# ranback_top.net
KiCad netlist of a schematic drawn in EAGLE
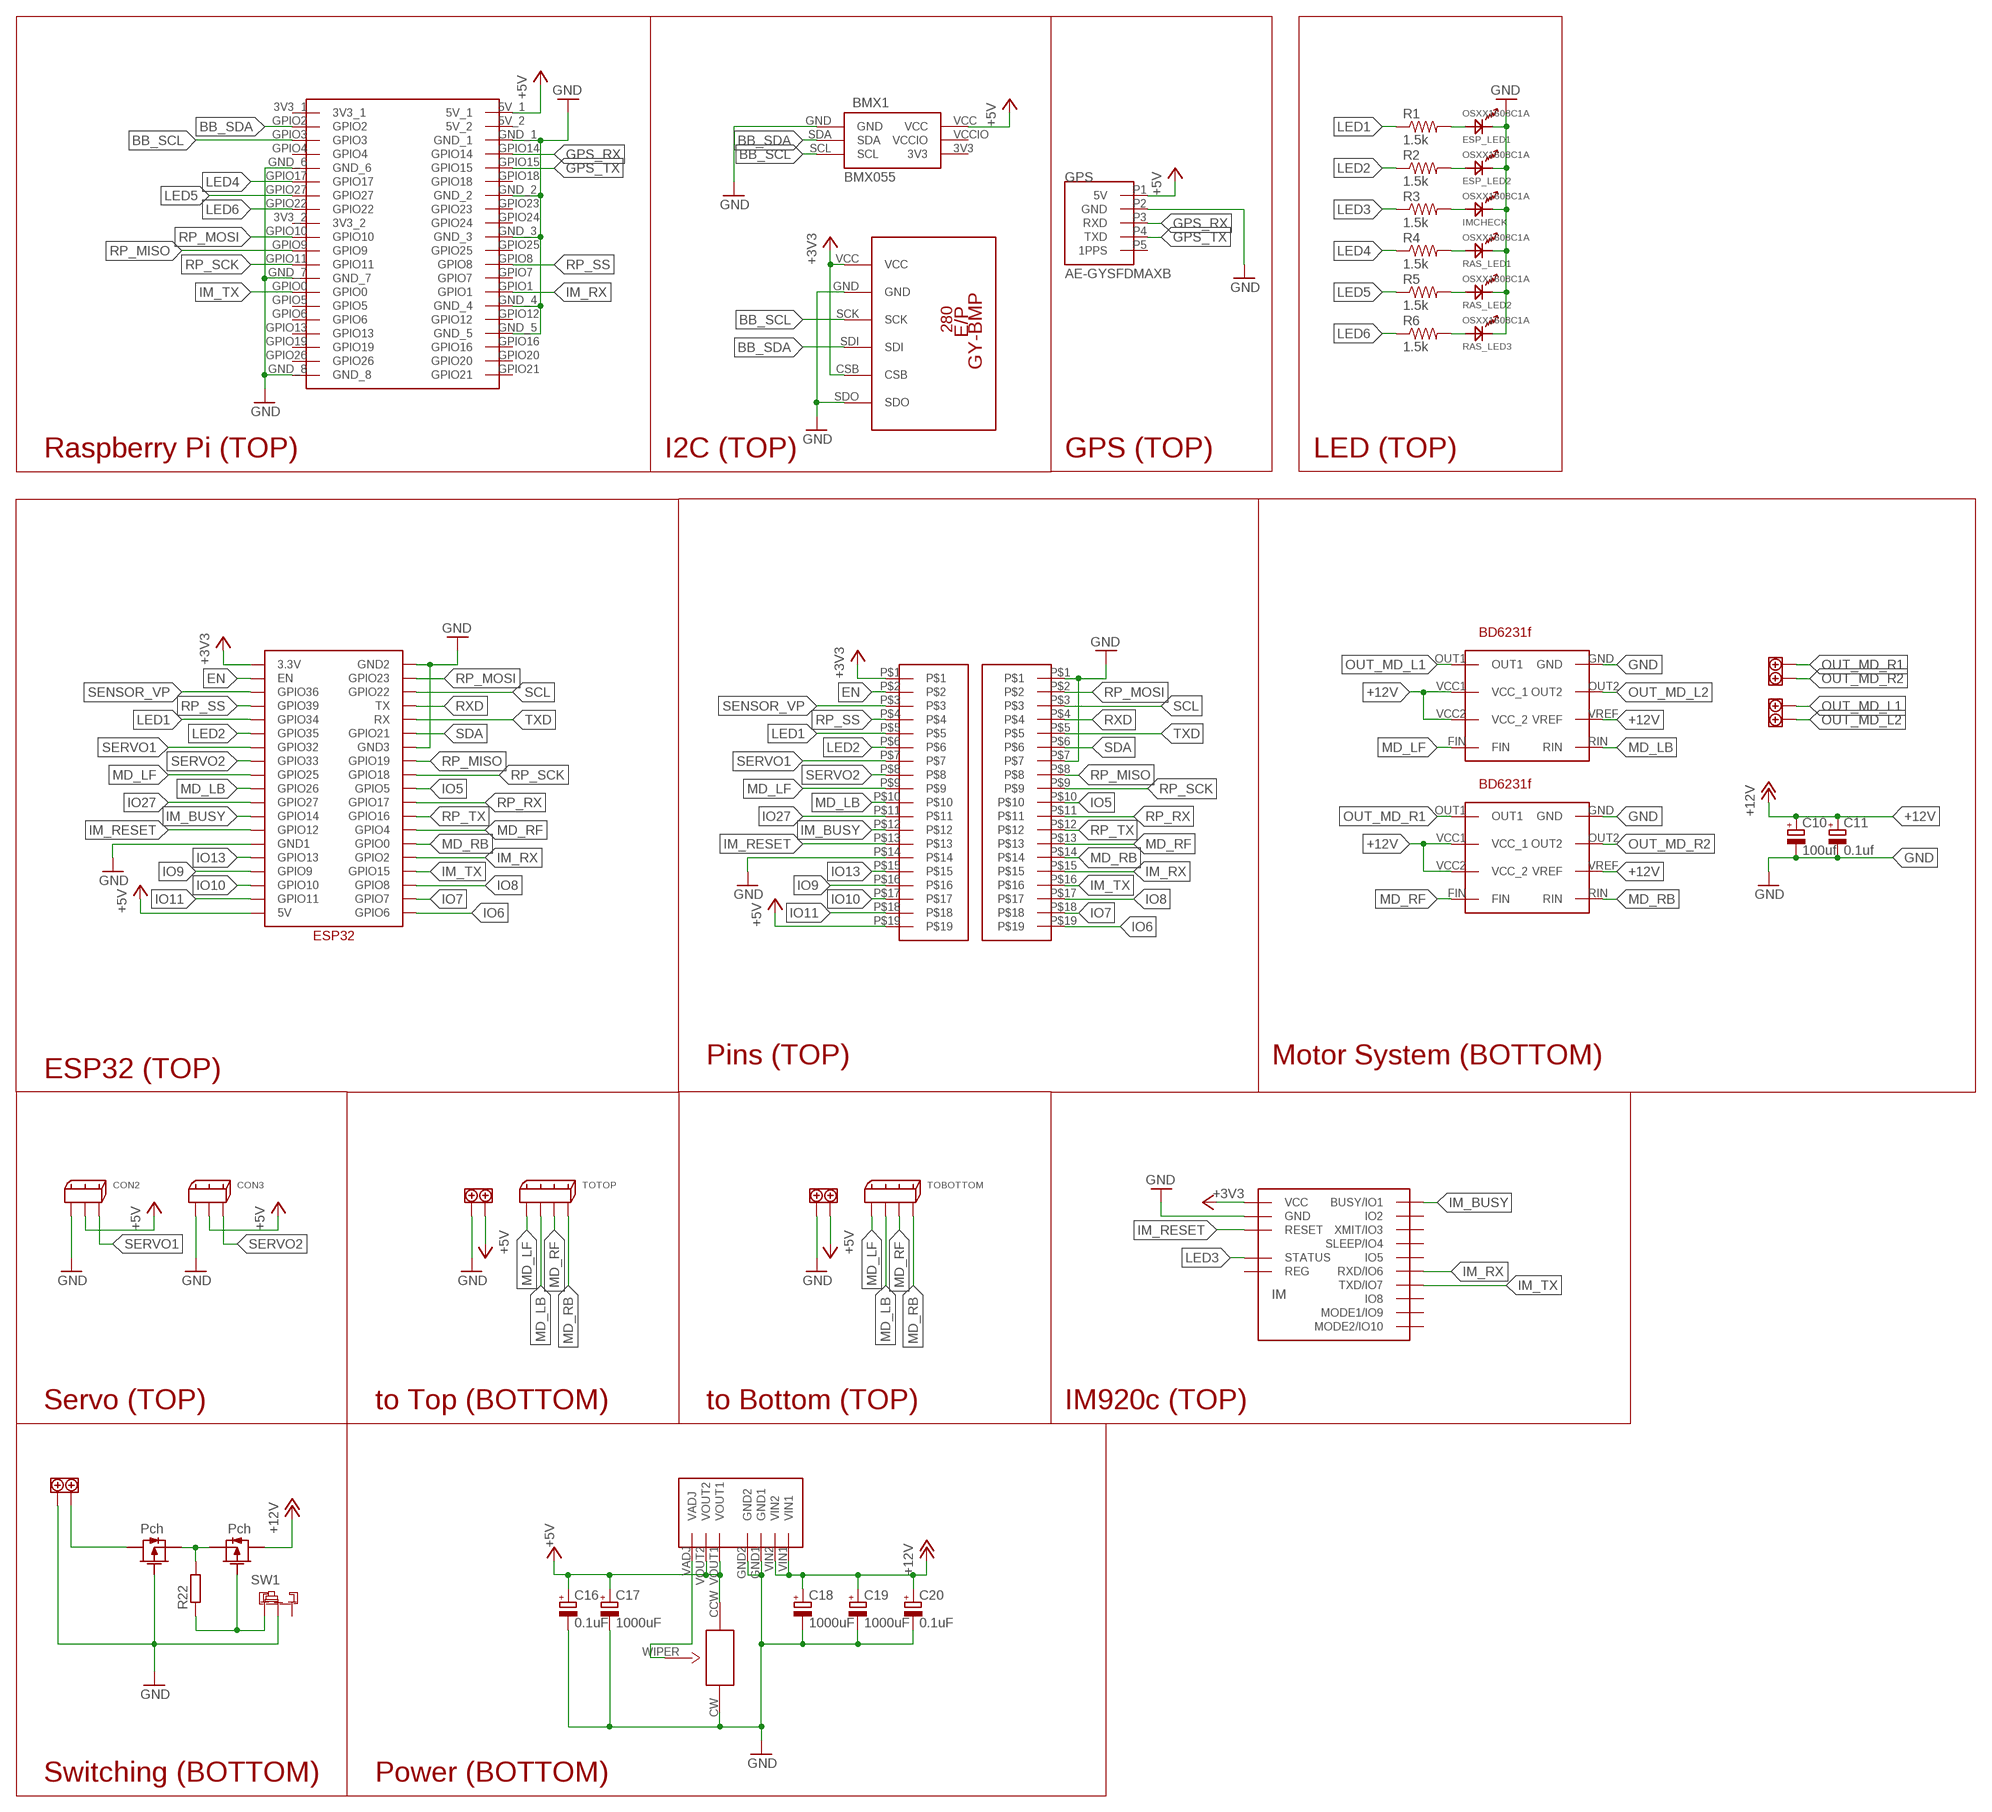
[diagram p0: schematic, sheet 1]

(export (version "E")
  (design (tool "Eeschema 10.0.6"))
  (components
    (comp (ref "100KR1")
      (value "100kR")
      (footprint "eagle-import:3362P")
      (libsource (lib "eagle-import") (part "3362P"))
    )
    (comp (ref "BMX1")
      (value "BMX055")
      (footprint "eagle-import:BMX055")
      (libsource (lib "eagle-import") (part "BMX055"))
    )
    (comp (ref "C10")
      (value "100uf")
      (footprint "eagle-import:E2,5-7")
      (libsource (lib "eagle-import") (part "CPOL-EUE2.5-7"))
    )
    (comp (ref "C11")
      (value "0.1uf")
      (footprint "eagle-import:E2,5-7")
      (libsource (lib "eagle-import") (part "CPOL-EUE2.5-7"))
    )
    (comp (ref "C16")
      (value "0.1uF")
      (footprint "eagle-import:E2,5-7")
      (libsource (lib "eagle-import") (part "CPOL-EUE2.5-7"))
    )
    (comp (ref "C17")
      (value "1000uF")
      (footprint "eagle-import:E5-10,5")
      (libsource (lib "eagle-import") (part "CPOL-EUE5-10.5"))
    )
    (comp (ref "C18")
      (value "1000uF")
      (footprint "eagle-import:E5-10,5")
      (libsource (lib "eagle-import") (part "CPOL-EUE5-10.5"))
    )
    (comp (ref "C19")
      (value "1000uF")
      (footprint "eagle-import:E5-10,5")
      (libsource (lib "eagle-import") (part "CPOL-EUE5-10.5"))
    )
    (comp (ref "C20")
      (value "0.1uF")
      (footprint "eagle-import:E2,5-7")
      (libsource (lib "eagle-import") (part "CPOL-EUE2.5-7"))
    )
    (comp (ref "CON2")
      (value "2.5_MINI-SPOX_3PIN")
      (footprint "eagle-import:2.5_MINI-SPOX_3PIN")
      (libsource (lib "eagle-import") (part "2.5_MINI-SPOX_3PIN"))
    )
    (comp (ref "CON3")
      (value "2.5_MINI-SPOX_3PIN")
      (footprint "eagle-import:2.5_MINI-SPOX_3PIN")
      (libsource (lib "eagle-import") (part "2.5_MINI-SPOX_3PIN"))
    )
    (comp (ref "ESP_LED1")
      (value "OSXX1608C1A")
      (footprint "eagle-import:OSXX1608C1A")
      (libsource (lib "eagle-import") (part "OSXX1608C1A"))
    )
    (comp (ref "ESP_LED2")
      (value "OSXX1608C1A")
      (footprint "eagle-import:OSXX1608C1A")
      (libsource (lib "eagle-import") (part "OSXX1608C1A"))
    )
    (comp (ref "GPS")
      (value "AE-GYSFDMAXB")
      (footprint "eagle-import:AE-GYSFDMAXB")
      (libsource (lib "eagle-import") (part "AE-GYSFDMAXB"))
    )
    (comp (ref "IM")
      (value "IM920C")
      (footprint "eagle-import:IM920C")
      (libsource (lib "eagle-import") (part "IM920C"))
    )
    (comp (ref "IMCHECK")
      (value "OSXX1608C1A")
      (footprint "eagle-import:OSXX1608C1A")
      (libsource (lib "eagle-import") (part "OSXX1608C1A"))
    )
    (comp (ref "MD_L")
      (value "BD6231F")
      (footprint "eagle-import:BD6231F")
      (libsource (lib "eagle-import") (part "BD6231F"))
    )
    (comp (ref "MD_R")
      (value "BD6231F")
      (footprint "eagle-import:BD6231F")
      (libsource (lib "eagle-import") (part "BD6231F"))
    )
    (comp (ref "PIN_L")
      (value "19_2.54")
      (footprint "eagle-import:19_2.54")
      (libsource (lib "eagle-import") (part "19_2.54"))
    )
    (comp (ref "PIN_R")
      (value "19_2.54")
      (footprint "eagle-import:19_2.54")
      (libsource (lib "eagle-import") (part "19_2.54"))
    )
    (comp (ref "R1")
      (value "1.5k")
      (footprint "eagle-import:R0603")
      (libsource (lib "eagle-import") (part "R-US_R0603"))
    )
    (comp (ref "R2")
      (value "1.5k")
      (footprint "eagle-import:R0603")
      (libsource (lib "eagle-import") (part "R-US_R0603"))
    )
    (comp (ref "R3")
      (value "1.5k")
      (footprint "eagle-import:R0603")
      (libsource (lib "eagle-import") (part "R-US_R0603"))
    )
    (comp (ref "R4")
      (value "1.5k")
      (footprint "eagle-import:R0603")
      (libsource (lib "eagle-import") (part "R-US_R0603"))
    )
    (comp (ref "R5")
      (value "1.5k")
      (footprint "eagle-import:R0603")
      (libsource (lib "eagle-import") (part "R-US_R0603"))
    )
    (comp (ref "R6")
      (value "1.5k")
      (footprint "eagle-import:R0603")
      (libsource (lib "eagle-import") (part "R-US_R0603"))
    )
    (comp (ref "R22")
      (value "R-EU_0207/10")
      (footprint "eagle-import:0207_10")
      (libsource (lib "eagle-import") (part "R-EU_0207/10"))
    )
    (comp (ref "RASPBERRYPI_4B")
      (value "RASPBERRYPI4B")
      (footprint "eagle-import:RASPBERRYPI4B")
      (libsource (lib "eagle-import") (part "RASPBERRYPI4B"))
    )
    (comp (ref "RAS_LED1")
      (value "OSXX1608C1A")
      (footprint "eagle-import:OSXX1608C1A")
      (libsource (lib "eagle-import") (part "OSXX1608C1A"))
    )
    (comp (ref "RAS_LED2")
      (value "OSXX1608C1A")
      (footprint "eagle-import:OSXX1608C1A")
      (libsource (lib "eagle-import") (part "OSXX1608C1A"))
    )
    (comp (ref "RAS_LED3")
      (value "OSXX1608C1A")
      (footprint "eagle-import:OSXX1608C1A")
      (libsource (lib "eagle-import") (part "OSXX1608C1A"))
    )
    (comp (ref "SW1")
      (value "SRIDE_SWITCH")
      (footprint "eagle-import:SRIDE_SWITCH")
      (libsource (lib "eagle-import") (part "SRIDE_SWITCH"))
    )
    (comp (ref "TM1")
      (value "TERMINAL_SLOPED_2PIN")
      (footprint "eagle-import:TERMINAL_SLOPED_2PIN")
      (libsource (lib "eagle-import") (part "TERMINAL_SLOPED_2PIN"))
    )
    (comp (ref "TM2")
      (value "TERMINAL_SLOPED_2PIN")
      (footprint "eagle-import:TERMINAL_SLOPED_2PIN")
      (libsource (lib "eagle-import") (part "TERMINAL_SLOPED_2PIN"))
    )
    (comp (ref "TM3")
      (value "TERMINAL_SLOPED_2PIN")
      (footprint "eagle-import:TERMINAL_SLOPED_2PIN")
      (libsource (lib "eagle-import") (part "TERMINAL_SLOPED_2PIN"))
    )
    (comp (ref "TM4")
      (value "TERMINAL_SLOPED_2PIN")
      (footprint "eagle-import:TERMINAL_SLOPED_2PIN")
      (libsource (lib "eagle-import") (part "TERMINAL_SLOPED_2PIN"))
    )
    (comp (ref "TM5")
      (value "TERMINAL_SLOPED_2PIN")
      (footprint "eagle-import:TERMINAL_SLOPED_2PIN")
      (libsource (lib "eagle-import") (part "TERMINAL_SLOPED_2PIN"))
    )
    (comp (ref "TOBOTTOM")
      (value "2.5_MINI-SPOX_4PIN")
      (footprint "eagle-import:2.5_MINI-SPOX_4PIN")
      (libsource (lib "eagle-import") (part "2.5_MINI-SPOX_4PIN"))
    )
    (comp (ref "TOTOP")
      (value "2.5_MINI-SPOX_4PIN")
      (footprint "eagle-import:2.5_MINI-SPOX_4PIN")
      (libsource (lib "eagle-import") (part "2.5_MINI-SPOX_4PIN"))
    )
    (comp (ref "U$2")
      (value "ESP32")
      (footprint "eagle-import:ESP32")
      (libsource (lib "eagle-import") (part "ESP32"))
    )
    (comp (ref "U$7")
      (value "2SJ681-PCH")
      (footprint "eagle-import:2SJ681")
      (libsource (lib "eagle-import") (part "2SJ681-PCH"))
    )
    (comp (ref "U$8")
      (value "5V3A_KIC-053")
      (footprint "eagle-import:5V3A_KIC-053")
      (libsource (lib "eagle-import") (part "5V3A_KIC-053"))
    )
    (comp (ref "U$9")
      (value "GY-BPM280")
      (footprint "eagle-import:GY-BMP280-FOOTPRINT")
      (libsource (lib "eagle-import") (part "GY-BPM280"))
    )
    (comp (ref "U$10")
      (value "2SJ681-PCH")
      (footprint "eagle-import:2SJ681")
      (libsource (lib "eagle-import") (part "2SJ681-PCH"))
    )
  )
  (nets
    (net (code "1") (name "+3V3") (class "Default")
      (node (ref "IM") (pin "$P17") (pinfunction "VCC_$P17") (pintype "bidirectional"))
      (node (ref "PIN_L") (pin "P$1") (pinfunction "P$1_P$1") (pintype "bidirectional"))
      (node (ref "U$2") (pin "3.3V") (pinfunction "3.3V_3.3V") (pintype "bidirectional"))
      (node (ref "U$9") (pin "CSB") (pinfunction "CSB_CSB") (pintype "bidirectional"))
      (node (ref "U$9") (pin "VCC") (pinfunction "VCC_VCC") (pintype "bidirectional"))
    )
    (net (code "2") (name "+5V") (class "Default")
      (node (ref "100KR1") (pin "CCW") (pinfunction "CCW_CCW") (pintype "bidirectional"))
      (node (ref "BMX1") (pin "VCC") (pinfunction "VCC_VCC") (pintype "power_in"))
      (node (ref "C16") (pin "+") (pinfunction "+_+") (pintype "passive"))
      (node (ref "C17") (pin "+") (pinfunction "+_+") (pintype "passive"))
      (node (ref "CON2") (pin "2") (pinfunction "2_2") (pintype "bidirectional"))
      (node (ref "CON3") (pin "2") (pinfunction "2_2") (pintype "bidirectional"))
      (node (ref "GPS") (pin "P1") (pinfunction "5V_P1") (pintype "bidirectional"))
      (node (ref "PIN_L") (pin "P$19") (pinfunction "P$19_P$19") (pintype "bidirectional"))
      (node (ref "RASPBERRYPI_4B") (pin "5V_1") (pinfunction "5V_1_5V_1") (pintype "bidirectional"))
      (node (ref "TM4") (pin "1") (pinfunction "1_1") (pintype "bidirectional"))
      (node (ref "TM5") (pin "1") (pinfunction "1_1") (pintype "bidirectional"))
      (node (ref "U$2") (pin "5V") (pinfunction "5V_5V") (pintype "bidirectional"))
      (node (ref "U$8") (pin "VOUT1") (pinfunction "VOUT1_VOUT1") (pintype "bidirectional"))
      (node (ref "U$8") (pin "VOUT2") (pinfunction "VOUT2_VOUT2") (pintype "bidirectional"))
    )
    (net (code "3") (name "+12V") (class "Default")
      (node (ref "C10") (pin "+") (pinfunction "+_+") (pintype "passive"))
      (node (ref "C11") (pin "+") (pinfunction "+_+") (pintype "passive"))
      (node (ref "C18") (pin "+") (pinfunction "+_+") (pintype "passive"))
      (node (ref "C19") (pin "+") (pinfunction "+_+") (pintype "passive"))
      (node (ref "C20") (pin "+") (pinfunction "+_+") (pintype "passive"))
      (node (ref "MD_L") (pin "VCC1") (pinfunction "VCC_1_VCC1") (pintype "bidirectional"))
      (node (ref "MD_L") (pin "VCC2") (pinfunction "VCC_2_VCC2") (pintype "bidirectional"))
      (node (ref "MD_L") (pin "VREF") (pinfunction "VREF_VREF") (pintype "bidirectional"))
      (node (ref "MD_R") (pin "VCC1") (pinfunction "VCC_1_VCC1") (pintype "bidirectional"))
      (node (ref "MD_R") (pin "VCC2") (pinfunction "VCC_2_VCC2") (pintype "bidirectional"))
      (node (ref "MD_R") (pin "VREF") (pinfunction "VREF_VREF") (pintype "bidirectional"))
      (node (ref "U$10") (pin "DRAIN") (pinfunction "DRAIN_DRAIN") (pintype "bidirectional"))
      (node (ref "U$8") (pin "VIN1") (pinfunction "VIN1_VIN1") (pintype "bidirectional"))
      (node (ref "U$8") (pin "VIN2") (pinfunction "VIN2_VIN2") (pintype "bidirectional"))
    )
    (net (code "4") (name "/3V3") (class "Default")
      (node (ref "BMX1") (pin "3V3") (pinfunction "3V3_3V3") (pintype "power_in"))
    )
    (net (code "5") (name "/VCCIO") (class "Default")
      (node (ref "BMX1") (pin "VCCIO") (pinfunction "VCCIO_VCCIO") (pintype "power_in"))
    )
    (net (code "6") (name "BB_SCL") (class "Default")
      (node (ref "BMX1") (pin "SCL") (pinfunction "SCL_SCL") (pintype "bidirectional"))
      (node (ref "RASPBERRYPI_4B") (pin "GPIO3") (pinfunction "GPIO3_GPIO3") (pintype "bidirectional"))
      (node (ref "U$9") (pin "SCK") (pinfunction "SCK_SCK") (pintype "bidirectional"))
    )
    (net (code "7") (name "BB_SDA") (class "Default")
      (node (ref "BMX1") (pin "SDA") (pinfunction "SDA_SDA") (pintype "bidirectional"))
      (node (ref "RASPBERRYPI_4B") (pin "GPIO2") (pinfunction "GPIO2_GPIO2") (pintype "bidirectional"))
      (node (ref "U$9") (pin "SDI") (pinfunction "SDI_SDI") (pintype "bidirectional"))
    )
    (net (code "8") (name "EN") (class "Default")
      (node (ref "PIN_L") (pin "P$2") (pinfunction "P$2_P$2") (pintype "bidirectional"))
      (node (ref "U$2") (pin "EN") (pinfunction "EN_EN") (pintype "bidirectional"))
    )
    (net (code "9") (name "GND") (class "Default")
      (node (ref "100KR1") (pin "CW") (pinfunction "CW_CW") (pintype "bidirectional"))
      (node (ref "BMX1") (pin "GND") (pinfunction "GND_GND") (pintype "power_in"))
      (node (ref "C10") (pin "-") (pinfunction "-_-") (pintype "passive"))
      (node (ref "C11") (pin "-") (pinfunction "-_-") (pintype "passive"))
      (node (ref "C16") (pin "-") (pinfunction "-_-") (pintype "passive"))
      (node (ref "C17") (pin "-") (pinfunction "-_-") (pintype "passive"))
      (node (ref "C18") (pin "-") (pinfunction "-_-") (pintype "passive"))
      (node (ref "C19") (pin "-") (pinfunction "-_-") (pintype "passive"))
      (node (ref "C20") (pin "-") (pinfunction "-_-") (pintype "passive"))
      (node (ref "CON2") (pin "1") (pinfunction "1_1") (pintype "bidirectional"))
      (node (ref "CON3") (pin "1") (pinfunction "1_1") (pintype "bidirectional"))
      (node (ref "ESP_LED1") (pin "CT") (pinfunction "CT_CT") (pintype "bidirectional"))
      (node (ref "ESP_LED2") (pin "CT") (pinfunction "CT_CT") (pintype "bidirectional"))
      (node (ref "GPS") (pin "P2") (pinfunction "GND_P2") (pintype "bidirectional"))
      (node (ref "IM") (pin "$P18") (pinfunction "GND_$P18") (pintype "bidirectional"))
      (node (ref "IMCHECK") (pin "CT") (pinfunction "CT_CT") (pintype "bidirectional"))
      (node (ref "MD_L") (pin "GND") (pinfunction "GND_GND") (pintype "bidirectional"))
      (node (ref "MD_R") (pin "GND") (pinfunction "GND_GND") (pintype "bidirectional"))
      (node (ref "PIN_L") (pin "P$14") (pinfunction "P$14_P$14") (pintype "bidirectional"))
      (node (ref "PIN_R") (pin "P$1") (pinfunction "P$1_P$1") (pintype "bidirectional"))
      (node (ref "PIN_R") (pin "P$7") (pinfunction "P$7_P$7") (pintype "bidirectional"))
      (node (ref "RASPBERRYPI_4B") (pin "GND_1") (pinfunction "GND_1_GND_1") (pintype "bidirectional"))
      (node (ref "RASPBERRYPI_4B") (pin "GND_2") (pinfunction "GND_2_GND_2") (pintype "bidirectional"))
      (node (ref "RASPBERRYPI_4B") (pin "GND_3") (pinfunction "GND_3_GND_3") (pintype "bidirectional"))
      (node (ref "RASPBERRYPI_4B") (pin "GND_4") (pinfunction "GND_4_GND_4") (pintype "bidirectional"))
      (node (ref "RASPBERRYPI_4B") (pin "GND_5") (pinfunction "GND_5_GND_5") (pintype "bidirectional"))
      (node (ref "RASPBERRYPI_4B") (pin "GND_6") (pinfunction "GND_6_GND_6") (pintype "bidirectional"))
      (node (ref "RASPBERRYPI_4B") (pin "GND_7") (pinfunction "GND_7_GND_7") (pintype "bidirectional"))
      (node (ref "RASPBERRYPI_4B") (pin "GND_8") (pinfunction "GND_8_GND_8") (pintype "bidirectional"))
      (node (ref "RAS_LED1") (pin "CT") (pinfunction "CT_CT") (pintype "bidirectional"))
      (node (ref "RAS_LED2") (pin "CT") (pinfunction "CT_CT") (pintype "bidirectional"))
      (node (ref "RAS_LED3") (pin "CT") (pinfunction "CT_CT") (pintype "bidirectional"))
      (node (ref "SW1") (pin "LR") (pinfunction "LR_LR") (pintype "bidirectional"))
      (node (ref "TM3") (pin "2") (pinfunction "2_2") (pintype "bidirectional"))
      (node (ref "TM4") (pin "2") (pinfunction "2_2") (pintype "bidirectional"))
      (node (ref "TM5") (pin "2") (pinfunction "2_2") (pintype "bidirectional"))
      (node (ref "U$2") (pin "GND1") (pinfunction "GND1_GND1") (pintype "bidirectional"))
      (node (ref "U$2") (pin "GND2") (pinfunction "GND2_GND2") (pintype "bidirectional"))
      (node (ref "U$2") (pin "GND3") (pinfunction "GND3_GND3") (pintype "bidirectional"))
      (node (ref "U$7") (pin "GATE") (pinfunction "GATE_GATE") (pintype "bidirectional"))
      (node (ref "U$8") (pin "GND1") (pinfunction "GND1_GND1") (pintype "bidirectional"))
      (node (ref "U$8") (pin "GND2") (pinfunction "GND2_GND2") (pintype "bidirectional"))
      (node (ref "U$9") (pin "GND") (pinfunction "GND_GND") (pintype "bidirectional"))
      (node (ref "U$9") (pin "SDO") (pinfunction "SDO_SDO") (pintype "bidirectional"))
    )
    (net (code "10") (name "GPS_RX") (class "Default")
      (node (ref "GPS") (pin "P3") (pinfunction "RXD_P3") (pintype "bidirectional"))
      (node (ref "RASPBERRYPI_4B") (pin "GPIO14") (pinfunction "GPIO14_GPIO14") (pintype "bidirectional"))
    )
    (net (code "11") (name "GPS_TX") (class "Default")
      (node (ref "GPS") (pin "P4") (pinfunction "TXD_P4") (pintype "bidirectional"))
      (node (ref "RASPBERRYPI_4B") (pin "GPIO15") (pinfunction "GPIO15_GPIO15") (pintype "bidirectional"))
    )
    (net (code "12") (name "IM_BUSY") (class "Default")
      (node (ref "IM") (pin "$P1") (pinfunction "BUSY/IO1_$P1") (pintype "bidirectional"))
      (node (ref "PIN_L") (pin "P$12") (pinfunction "P$12_P$12") (pintype "bidirectional"))
      (node (ref "U$2") (pin "GPIO14") (pinfunction "GPIO14_GPIO14") (pintype "bidirectional"))
    )
    (net (code "13") (name "IM_RESET") (class "Default")
      (node (ref "IM") (pin "$P19") (pinfunction "RESET_$P19") (pintype "bidirectional"))
      (node (ref "PIN_L") (pin "P$13") (pinfunction "P$13_P$13") (pintype "bidirectional"))
      (node (ref "U$2") (pin "GPIO12") (pinfunction "GPIO12_GPIO12") (pintype "bidirectional"))
    )
    (net (code "14") (name "IM_RX") (class "Default")
      (node (ref "IM") (pin "$P6") (pinfunction "RXD/IO6_$P6") (pintype "bidirectional"))
      (node (ref "PIN_R") (pin "P$15") (pinfunction "P$15_P$15") (pintype "bidirectional"))
      (node (ref "RASPBERRYPI_4B") (pin "GPIO1") (pinfunction "GPIO1_GPIO1") (pintype "bidirectional"))
      (node (ref "U$2") (pin "GPIO2") (pinfunction "GPIO2_GPIO2") (pintype "bidirectional"))
    )
    (net (code "15") (name "IM_TX") (class "Default")
      (node (ref "IM") (pin "$P7") (pinfunction "TXD/IO7_$P7") (pintype "bidirectional"))
      (node (ref "PIN_R") (pin "P$16") (pinfunction "P$16_P$16") (pintype "bidirectional"))
      (node (ref "RASPBERRYPI_4B") (pin "GPIO0") (pinfunction "GPIO0_GPIO0") (pintype "bidirectional"))
      (node (ref "U$2") (pin "GPIO15") (pinfunction "GPIO15_GPIO15") (pintype "bidirectional"))
    )
    (net (code "16") (name "IO5") (class "Default")
      (node (ref "PIN_R") (pin "P$10") (pinfunction "P$10_P$10") (pintype "bidirectional"))
      (node (ref "U$2") (pin "GPIO5") (pinfunction "GPIO5_GPIO5") (pintype "bidirectional"))
    )
    (net (code "17") (name "IO6") (class "Default")
      (node (ref "PIN_R") (pin "P$19") (pinfunction "P$19_P$19") (pintype "bidirectional"))
      (node (ref "U$2") (pin "GPIO6") (pinfunction "GPIO6_GPIO6") (pintype "bidirectional"))
    )
    (net (code "18") (name "IO7") (class "Default")
      (node (ref "PIN_R") (pin "P$18") (pinfunction "P$18_P$18") (pintype "bidirectional"))
      (node (ref "U$2") (pin "GPIO7") (pinfunction "GPIO7_GPIO7") (pintype "bidirectional"))
    )
    (net (code "19") (name "IO8") (class "Default")
      (node (ref "PIN_R") (pin "P$17") (pinfunction "P$17_P$17") (pintype "bidirectional"))
      (node (ref "U$2") (pin "GPIO8") (pinfunction "GPIO8_GPIO8") (pintype "bidirectional"))
    )
    (net (code "20") (name "IO9") (class "Default")
      (node (ref "PIN_L") (pin "P$16") (pinfunction "P$16_P$16") (pintype "bidirectional"))
      (node (ref "U$2") (pin "GPIO9") (pinfunction "GPIO9_GPIO9") (pintype "bidirectional"))
    )
    (net (code "21") (name "IO10") (class "Default")
      (node (ref "PIN_L") (pin "P$17") (pinfunction "P$17_P$17") (pintype "bidirectional"))
      (node (ref "U$2") (pin "GPIO10") (pinfunction "GPIO10_GPIO10") (pintype "bidirectional"))
    )
    (net (code "22") (name "IO11") (class "Default")
      (node (ref "PIN_L") (pin "P$18") (pinfunction "P$18_P$18") (pintype "bidirectional"))
      (node (ref "U$2") (pin "GPIO11") (pinfunction "GPIO11_GPIO11") (pintype "bidirectional"))
    )
    (net (code "23") (name "IO13") (class "Default")
      (node (ref "PIN_L") (pin "P$15") (pinfunction "P$15_P$15") (pintype "bidirectional"))
      (node (ref "U$2") (pin "GPIO13") (pinfunction "GPIO13_GPIO13") (pintype "bidirectional"))
    )
    (net (code "24") (name "IO27") (class "Default")
      (node (ref "PIN_L") (pin "P$11") (pinfunction "P$11_P$11") (pintype "bidirectional"))
      (node (ref "U$2") (pin "GPIO27") (pinfunction "GPIO27_GPIO27") (pintype "bidirectional"))
    )
    (net (code "25") (name "LED1") (class "Default")
      (node (ref "PIN_L") (pin "P$5") (pinfunction "P$5_P$5") (pintype "bidirectional"))
      (node (ref "R1") (pin "1") (pinfunction "1_1") (pintype "passive"))
      (node (ref "U$2") (pin "GPIO34") (pinfunction "GPIO34_GPIO34") (pintype "bidirectional"))
    )
    (net (code "26") (name "LED2") (class "Default")
      (node (ref "PIN_L") (pin "P$6") (pinfunction "P$6_P$6") (pintype "bidirectional"))
      (node (ref "R2") (pin "1") (pinfunction "1_1") (pintype "passive"))
      (node (ref "U$2") (pin "GPIO35") (pinfunction "GPIO35_GPIO35") (pintype "bidirectional"))
    )
    (net (code "27") (name "LED3") (class "Default")
      (node (ref "IM") (pin "$P15") (pinfunction "STATUS_$P15") (pintype "bidirectional"))
      (node (ref "R3") (pin "1") (pinfunction "1_1") (pintype "passive"))
    )
    (net (code "28") (name "LED4") (class "Default")
      (node (ref "R4") (pin "1") (pinfunction "1_1") (pintype "passive"))
      (node (ref "RASPBERRYPI_4B") (pin "GPIO17") (pinfunction "GPIO17_GPIO17") (pintype "bidirectional"))
    )
    (net (code "29") (name "LED5") (class "Default")
      (node (ref "R5") (pin "1") (pinfunction "1_1") (pintype "passive"))
      (node (ref "RASPBERRYPI_4B") (pin "GPIO27") (pinfunction "GPIO27_GPIO27") (pintype "bidirectional"))
    )
    (net (code "30") (name "LED6") (class "Default")
      (node (ref "R6") (pin "1") (pinfunction "1_1") (pintype "passive"))
      (node (ref "RASPBERRYPI_4B") (pin "GPIO22") (pinfunction "GPIO22_GPIO22") (pintype "bidirectional"))
    )
    (net (code "31") (name "MD_LB") (class "Default")
      (node (ref "MD_L") (pin "RIN") (pinfunction "RIN_RIN") (pintype "bidirectional"))
      (node (ref "PIN_L") (pin "P$10") (pinfunction "P$10_P$10") (pintype "bidirectional"))
      (node (ref "TOBOTTOM") (pin "P$2") (pinfunction "2_P$2") (pintype "bidirectional"))
      (node (ref "TOTOP") (pin "P$2") (pinfunction "2_P$2") (pintype "bidirectional"))
      (node (ref "U$2") (pin "GPIO26") (pinfunction "GPIO26_GPIO26") (pintype "bidirectional"))
    )
    (net (code "32") (name "MD_LF") (class "Default")
      (node (ref "MD_L") (pin "FIN") (pinfunction "FIN_FIN") (pintype "bidirectional"))
      (node (ref "PIN_L") (pin "P$9") (pinfunction "P$9_P$9") (pintype "bidirectional"))
      (node (ref "TOBOTTOM") (pin "P$1") (pinfunction "1_P$1") (pintype "bidirectional"))
      (node (ref "TOTOP") (pin "P$1") (pinfunction "1_P$1") (pintype "bidirectional"))
      (node (ref "U$2") (pin "GPIO25") (pinfunction "GPIO25_GPIO25") (pintype "bidirectional"))
    )
    (net (code "33") (name "MD_RB") (class "Default")
      (node (ref "MD_R") (pin "RIN") (pinfunction "RIN_RIN") (pintype "bidirectional"))
      (node (ref "PIN_R") (pin "P$14") (pinfunction "P$14_P$14") (pintype "bidirectional"))
      (node (ref "TOBOTTOM") (pin "P$4") (pinfunction "4_P$4") (pintype "bidirectional"))
      (node (ref "TOTOP") (pin "P$4") (pinfunction "4_P$4") (pintype "bidirectional"))
      (node (ref "U$2") (pin "GPIO0") (pinfunction "GPIO0_GPIO0") (pintype "bidirectional"))
    )
    (net (code "34") (name "MD_RF") (class "Default")
      (node (ref "MD_R") (pin "FIN") (pinfunction "FIN_FIN") (pintype "bidirectional"))
      (node (ref "PIN_R") (pin "P$13") (pinfunction "P$13_P$13") (pintype "bidirectional"))
      (node (ref "TOBOTTOM") (pin "P$3") (pinfunction "3_P$3") (pintype "bidirectional"))
      (node (ref "TOTOP") (pin "P$3") (pinfunction "3_P$3") (pintype "bidirectional"))
      (node (ref "U$2") (pin "GPIO4") (pinfunction "GPIO4_GPIO4") (pintype "bidirectional"))
    )
    (net (code "35") (name "Net-(100KR1-PadWIPER)") (class "Default")
      (node (ref "100KR1") (pin "WIPER") (pinfunction "WIPER_WIPER") (pintype "bidirectional"))
      (node (ref "U$8") (pin "VADJ") (pinfunction "VADJ_VADJ") (pintype "bidirectional"))
    )
    (net (code "36") (name "Net-(ESP_LED1-PadAN)") (class "Default")
      (node (ref "ESP_LED1") (pin "AN") (pinfunction "AN_AN") (pintype "bidirectional"))
      (node (ref "R1") (pin "2") (pinfunction "2_2") (pintype "passive"))
    )
    (net (code "37") (name "Net-(ESP_LED2-PadAN)") (class "Default")
      (node (ref "ESP_LED2") (pin "AN") (pinfunction "AN_AN") (pintype "bidirectional"))
      (node (ref "R2") (pin "2") (pinfunction "2_2") (pintype "passive"))
    )
    (net (code "38") (name "Net-(IMCHECK-PadAN)") (class "Default")
      (node (ref "IMCHECK") (pin "AN") (pinfunction "AN_AN") (pintype "bidirectional"))
      (node (ref "R3") (pin "2") (pinfunction "2_2") (pintype "passive"))
    )
    (net (code "39") (name "Net-(R4-Pad2)") (class "Default")
      (node (ref "R4") (pin "2") (pinfunction "2_2") (pintype "passive"))
      (node (ref "RAS_LED1") (pin "AN") (pinfunction "AN_AN") (pintype "bidirectional"))
    )
    (net (code "40") (name "Net-(R5-Pad2)") (class "Default")
      (node (ref "R5") (pin "2") (pinfunction "2_2") (pintype "passive"))
      (node (ref "RAS_LED2") (pin "AN") (pinfunction "AN_AN") (pintype "bidirectional"))
    )
    (net (code "41") (name "Net-(R6-Pad2)") (class "Default")
      (node (ref "R6") (pin "2") (pinfunction "2_2") (pintype "passive"))
      (node (ref "RAS_LED3") (pin "AN") (pinfunction "AN_AN") (pintype "bidirectional"))
    )
    (net (code "42") (name "Net-(R22-Pad1)") (class "Default")
      (node (ref "R22") (pin "1") (pinfunction "1_1") (pintype "passive"))
      (node (ref "SW1") (pin "L") (pinfunction "L_L") (pintype "bidirectional"))
      (node (ref "U$10") (pin "GATE") (pinfunction "GATE_GATE") (pintype "bidirectional"))
    )
    (net (code "43") (name "Net-(R22-Pad2)") (class "Default")
      (node (ref "R22") (pin "2") (pinfunction "2_2") (pintype "passive"))
      (node (ref "U$10") (pin "SOURCE") (pinfunction "SOURCE_SOURCE") (pintype "bidirectional"))
      (node (ref "U$7") (pin "SOURCE") (pinfunction "SOURCE_SOURCE") (pintype "bidirectional"))
    )
    (net (code "44") (name "Net-(TM3-Pad1)") (class "Default")
      (node (ref "TM3") (pin "1") (pinfunction "1_1") (pintype "bidirectional"))
      (node (ref "U$7") (pin "DRAIN") (pinfunction "DRAIN_DRAIN") (pintype "bidirectional"))
    )
    (net (code "45") (name "OUT_MD_L1") (class "Default")
      (node (ref "MD_L") (pin "OUT1") (pinfunction "OUT1_OUT1") (pintype "bidirectional"))
      (node (ref "TM2") (pin "1") (pinfunction "1_1") (pintype "bidirectional"))
    )
    (net (code "46") (name "OUT_MD_L2") (class "Default")
      (node (ref "MD_L") (pin "OUT2") (pinfunction "OUT2_OUT2") (pintype "bidirectional"))
      (node (ref "TM2") (pin "2") (pinfunction "2_2") (pintype "bidirectional"))
    )
    (net (code "47") (name "OUT_MD_R1") (class "Default")
      (node (ref "MD_R") (pin "OUT1") (pinfunction "OUT1_OUT1") (pintype "bidirectional"))
      (node (ref "TM1") (pin "1") (pinfunction "1_1") (pintype "bidirectional"))
    )
    (net (code "48") (name "OUT_MD_R2") (class "Default")
      (node (ref "MD_R") (pin "OUT2") (pinfunction "OUT2_OUT2") (pintype "bidirectional"))
      (node (ref "TM1") (pin "2") (pinfunction "2_2") (pintype "bidirectional"))
    )
    (net (code "49") (name "RP_MISO") (class "Default")
      (node (ref "PIN_R") (pin "P$8") (pinfunction "P$8_P$8") (pintype "bidirectional"))
      (node (ref "RASPBERRYPI_4B") (pin "GPIO9") (pinfunction "GPIO9_GPIO9") (pintype "bidirectional"))
      (node (ref "U$2") (pin "GPIO19") (pinfunction "GPIO19_GPIO19") (pintype "bidirectional"))
    )
    (net (code "50") (name "RP_MOSI") (class "Default")
      (node (ref "PIN_R") (pin "P$2") (pinfunction "P$2_P$2") (pintype "bidirectional"))
      (node (ref "RASPBERRYPI_4B") (pin "GPIO10") (pinfunction "GPIO10_GPIO10") (pintype "bidirectional"))
      (node (ref "U$2") (pin "GPIO23") (pinfunction "GPIO23_GPIO23") (pintype "bidirectional"))
    )
    (net (code "51") (name "RP_RX") (class "Default")
      (node (ref "PIN_R") (pin "P$11") (pinfunction "P$11_P$11") (pintype "bidirectional"))
      (node (ref "U$2") (pin "GPIO17") (pinfunction "GPIO17_GPIO17") (pintype "bidirectional"))
    )
    (net (code "52") (name "RP_SCK") (class "Default")
      (node (ref "PIN_R") (pin "P$9") (pinfunction "P$9_P$9") (pintype "bidirectional"))
      (node (ref "RASPBERRYPI_4B") (pin "GPIO11") (pinfunction "GPIO11_GPIO11") (pintype "bidirectional"))
      (node (ref "U$2") (pin "GPIO18") (pinfunction "GPIO18_GPIO18") (pintype "bidirectional"))
    )
    (net (code "53") (name "RP_SS") (class "Default")
      (node (ref "PIN_L") (pin "P$4") (pinfunction "P$4_P$4") (pintype "bidirectional"))
      (node (ref "RASPBERRYPI_4B") (pin "GPIO8") (pinfunction "GPIO8_GPIO8") (pintype "bidirectional"))
      (node (ref "U$2") (pin "GPIO39") (pinfunction "GPIO39_GPIO39") (pintype "bidirectional"))
    )
    (net (code "54") (name "RP_TX") (class "Default")
      (node (ref "PIN_R") (pin "P$12") (pinfunction "P$12_P$12") (pintype "bidirectional"))
      (node (ref "U$2") (pin "GPIO16") (pinfunction "GPIO16_GPIO16") (pintype "bidirectional"))
    )
    (net (code "55") (name "RXD") (class "Default")
      (node (ref "PIN_R") (pin "P$4") (pinfunction "P$4_P$4") (pintype "bidirectional"))
      (node (ref "U$2") (pin "TX") (pinfunction "TX_TX") (pintype "bidirectional"))
    )
    (net (code "56") (name "SCL") (class "Default")
      (node (ref "PIN_R") (pin "P$3") (pinfunction "P$3_P$3") (pintype "bidirectional"))
      (node (ref "U$2") (pin "GPIO22") (pinfunction "GPIO22_GPIO22") (pintype "bidirectional"))
    )
    (net (code "57") (name "SDA") (class "Default")
      (node (ref "PIN_R") (pin "P$6") (pinfunction "P$6_P$6") (pintype "bidirectional"))
      (node (ref "U$2") (pin "GPIO21") (pinfunction "GPIO21_GPIO21") (pintype "bidirectional"))
    )
    (net (code "58") (name "SENSOR_VP") (class "Default")
      (node (ref "PIN_L") (pin "P$3") (pinfunction "P$3_P$3") (pintype "bidirectional"))
      (node (ref "U$2") (pin "GPIO36") (pinfunction "GPIO36_GPIO36") (pintype "bidirectional"))
    )
    (net (code "59") (name "SERVO1") (class "Default")
      (node (ref "CON2") (pin "3") (pinfunction "3_3") (pintype "bidirectional"))
      (node (ref "PIN_L") (pin "P$7") (pinfunction "P$7_P$7") (pintype "bidirectional"))
      (node (ref "U$2") (pin "GPIO32") (pinfunction "GPIO32_GPIO32") (pintype "bidirectional"))
    )
    (net (code "60") (name "SERVO2") (class "Default")
      (node (ref "CON3") (pin "3") (pinfunction "3_3") (pintype "bidirectional"))
      (node (ref "PIN_L") (pin "P$8") (pinfunction "P$8_P$8") (pintype "bidirectional"))
      (node (ref "U$2") (pin "GPIO33") (pinfunction "GPIO33_GPIO33") (pintype "bidirectional"))
    )
    (net (code "61") (name "TXD") (class "Default")
      (node (ref "PIN_R") (pin "P$5") (pinfunction "P$5_P$5") (pintype "bidirectional"))
      (node (ref "U$2") (pin "RX") (pinfunction "RX_RX") (pintype "bidirectional"))
    )
    (net (code "62") (name "unconnected-(GPS-1PPS-PadP5)") (class "Default")
      (node (ref "GPS") (pin "P5") (pinfunction "1PPS_P5") (pintype "bidirectional"))
    )
    (net (code "63") (name "unconnected-(IM-IO2-Pad$P2)") (class "Default")
      (node (ref "IM") (pin "$P2") (pinfunction "IO2_$P2") (pintype "bidirectional"))
    )
    (net (code "64") (name "unconnected-(IM-IO5-Pad$P5)") (class "Default")
      (node (ref "IM") (pin "$P5") (pinfunction "IO5_$P5") (pintype "bidirectional"))
    )
    (net (code "65") (name "unconnected-(IM-IO8-Pad$P8)") (class "Default")
      (node (ref "IM") (pin "$P8") (pinfunction "IO8_$P8") (pintype "bidirectional"))
    )
    (net (code "66") (name "unconnected-(IM-MODE1{slash}IO9-Pad$P9)") (class "Default")
      (node (ref "IM") (pin "$P9") (pinfunction "MODE1/IO9_$P9") (pintype "bidirectional"))
    )
    (net (code "67") (name "unconnected-(IM-MODE2{slash}IO10-Pad$P10)") (class "Default")
      (node (ref "IM") (pin "$P10") (pinfunction "MODE2/IO10_$P10") (pintype "bidirectional"))
    )
    (net (code "68") (name "unconnected-(IM-REG-Pad$P16)") (class "Default")
      (node (ref "IM") (pin "$P16") (pinfunction "REG_$P16") (pintype "bidirectional"))
    )
    (net (code "69") (name "unconnected-(IM-SLEEP{slash}IO4-Pad$P4)") (class "Default")
      (node (ref "IM") (pin "$P4") (pinfunction "SLEEP/IO4_$P4") (pintype "bidirectional"))
    )
    (net (code "70") (name "unconnected-(IM-XMIT{slash}IO3-Pad$P3)") (class "Default")
      (node (ref "IM") (pin "$P3") (pinfunction "XMIT/IO3_$P3") (pintype "bidirectional"))
    )
    (net (code "71") (name "unconnected-(RASPBERRYPI_4B-Pad3V3_1)") (class "Default")
      (node (ref "RASPBERRYPI_4B") (pin "3V3_1") (pinfunction "3V3_1_3V3_1") (pintype "bidirectional"))
    )
    (net (code "72") (name "unconnected-(RASPBERRYPI_4B-Pad3V3_2)") (class "Default")
      (node (ref "RASPBERRYPI_4B") (pin "3V3_2") (pinfunction "3V3_2_3V3_2") (pintype "bidirectional"))
    )
    (net (code "73") (name "unconnected-(RASPBERRYPI_4B-Pad5V_2)") (class "Default")
      (node (ref "RASPBERRYPI_4B") (pin "5V_2") (pinfunction "5V_2_5V_2") (pintype "bidirectional"))
    )
    (net (code "74") (name "unconnected-(RASPBERRYPI_4B-PadGPIO4)") (class "Default")
      (node (ref "RASPBERRYPI_4B") (pin "GPIO4") (pinfunction "GPIO4_GPIO4") (pintype "bidirectional"))
    )
    (net (code "75") (name "unconnected-(RASPBERRYPI_4B-PadGPIO5)") (class "Default")
      (node (ref "RASPBERRYPI_4B") (pin "GPIO5") (pinfunction "GPIO5_GPIO5") (pintype "bidirectional"))
    )
    (net (code "76") (name "unconnected-(RASPBERRYPI_4B-PadGPIO6)") (class "Default")
      (node (ref "RASPBERRYPI_4B") (pin "GPIO6") (pinfunction "GPIO6_GPIO6") (pintype "bidirectional"))
    )
    (net (code "77") (name "unconnected-(RASPBERRYPI_4B-PadGPIO7)") (class "Default")
      (node (ref "RASPBERRYPI_4B") (pin "GPIO7") (pinfunction "GPIO7_GPIO7") (pintype "bidirectional"))
    )
    (net (code "78") (name "unconnected-(RASPBERRYPI_4B-PadGPIO12)") (class "Default")
      (node (ref "RASPBERRYPI_4B") (pin "GPIO12") (pinfunction "GPIO12_GPIO12") (pintype "bidirectional"))
    )
    (net (code "79") (name "unconnected-(RASPBERRYPI_4B-PadGPIO13)") (class "Default")
      (node (ref "RASPBERRYPI_4B") (pin "GPIO13") (pinfunction "GPIO13_GPIO13") (pintype "bidirectional"))
    )
    (net (code "80") (name "unconnected-(RASPBERRYPI_4B-PadGPIO16)") (class "Default")
      (node (ref "RASPBERRYPI_4B") (pin "GPIO16") (pinfunction "GPIO16_GPIO16") (pintype "bidirectional"))
    )
    (net (code "81") (name "unconnected-(RASPBERRYPI_4B-PadGPIO18)") (class "Default")
      (node (ref "RASPBERRYPI_4B") (pin "GPIO18") (pinfunction "GPIO18_GPIO18") (pintype "bidirectional"))
    )
    (net (code "82") (name "unconnected-(RASPBERRYPI_4B-PadGPIO19)") (class "Default")
      (node (ref "RASPBERRYPI_4B") (pin "GPIO19") (pinfunction "GPIO19_GPIO19") (pintype "bidirectional"))
    )
    (net (code "83") (name "unconnected-(RASPBERRYPI_4B-PadGPIO20)") (class "Default")
      (node (ref "RASPBERRYPI_4B") (pin "GPIO20") (pinfunction "GPIO20_GPIO20") (pintype "bidirectional"))
    )
    (net (code "84") (name "unconnected-(RASPBERRYPI_4B-PadGPIO21)") (class "Default")
      (node (ref "RASPBERRYPI_4B") (pin "GPIO21") (pinfunction "GPIO21_GPIO21") (pintype "bidirectional"))
    )
    (net (code "85") (name "unconnected-(RASPBERRYPI_4B-PadGPIO23)") (class "Default")
      (node (ref "RASPBERRYPI_4B") (pin "GPIO23") (pinfunction "GPIO23_GPIO23") (pintype "bidirectional"))
    )
    (net (code "86") (name "unconnected-(RASPBERRYPI_4B-PadGPIO24)") (class "Default")
      (node (ref "RASPBERRYPI_4B") (pin "GPIO24") (pinfunction "GPIO24_GPIO24") (pintype "bidirectional"))
    )
    (net (code "87") (name "unconnected-(RASPBERRYPI_4B-PadGPIO25)") (class "Default")
      (node (ref "RASPBERRYPI_4B") (pin "GPIO25") (pinfunction "GPIO25_GPIO25") (pintype "bidirectional"))
    )
    (net (code "88") (name "unconnected-(RASPBERRYPI_4B-PadGPIO26)") (class "Default")
      (node (ref "RASPBERRYPI_4B") (pin "GPIO26") (pinfunction "GPIO26_GPIO26") (pintype "bidirectional"))
    )
    (net (code "89") (name "unconnected-(SW1-PadR)") (class "Default")
      (node (ref "SW1") (pin "R") (pinfunction "R_R") (pintype "bidirectional"))
    )
  )
)
